# Microcontroller_1_2.net
KiCad netlist of a schematic drawn in EAGLE
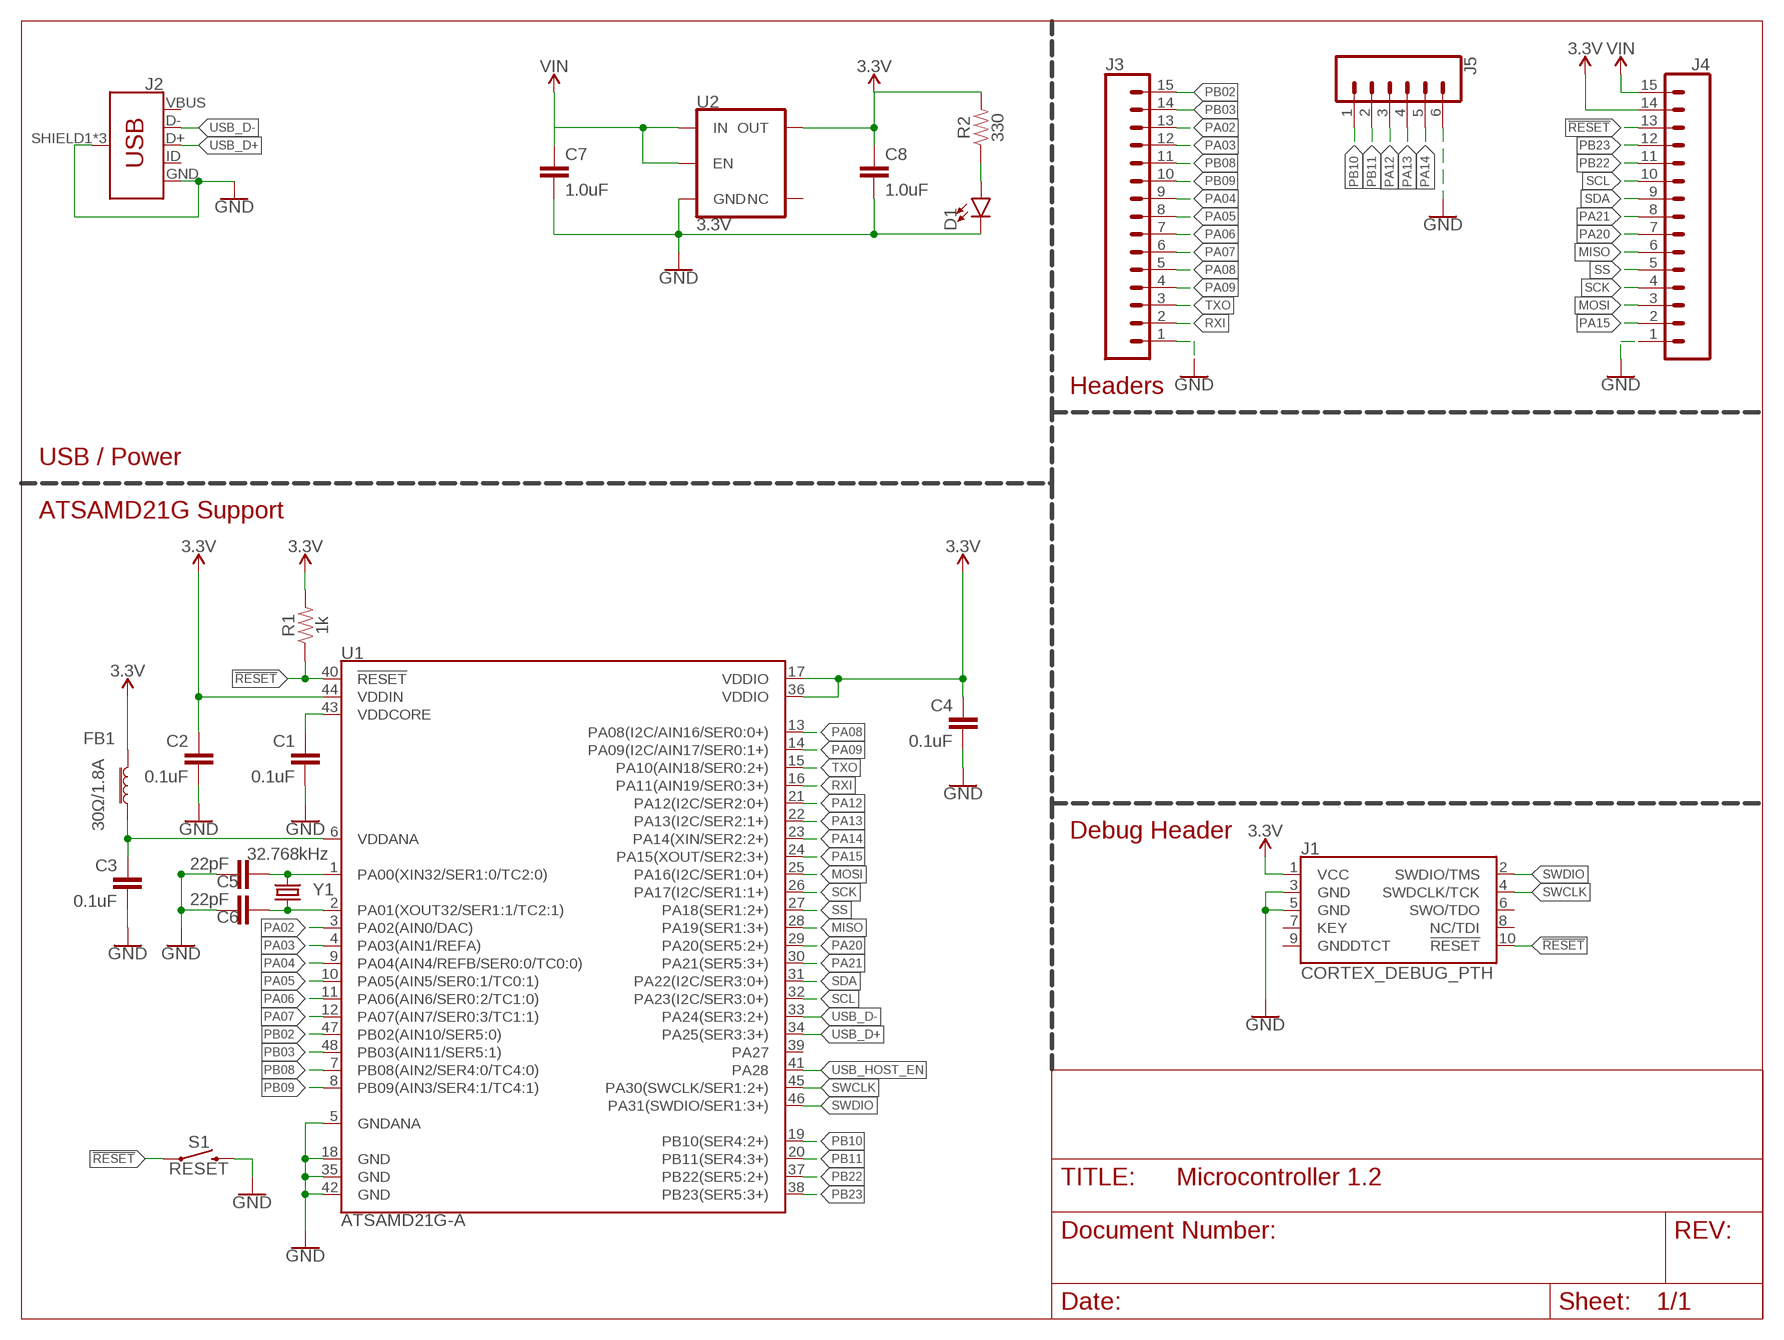
[diagram p0: schematic, sheet 1]

(export (version "E")
  (design (tool "Eeschema 10.0.6"))
  (components
    (comp (ref "C1")
      (value "0.1uF")
      (footprint "eagle-import:CAP-PTH-SMALL-KIT")
      (libsource (lib "eagle-import") (part "0.1UF-KIT-EZ-50V-20%"))
    )
    (comp (ref "C2")
      (value "0.1uF")
      (footprint "eagle-import:CAP-PTH-SMALL-KIT")
      (libsource (lib "eagle-import") (part "0.1UF-KIT-EZ-50V-20%"))
    )
    (comp (ref "C3")
      (value "0.1uF")
      (footprint "eagle-import:CAP-PTH-SMALL-KIT")
      (libsource (lib "eagle-import") (part "0.1UF-KIT-EZ-50V-20%"))
    )
    (comp (ref "C4")
      (value "0.1uF")
      (footprint "eagle-import:CAP-PTH-SMALL-KIT")
      (libsource (lib "eagle-import") (part "0.1UF-KIT-EZ-50V-20%"))
    )
    (comp (ref "C5")
      (value "22pF")
      (footprint "eagle-import:CAP-PTH-SMALL-KIT")
      (libsource (lib "eagle-import") (part "0.1UF-KIT-EZ-50V-20%"))
    )
    (comp (ref "C6")
      (value "22pF")
      (footprint "eagle-import:CAP-PTH-SMALL-KIT")
      (libsource (lib "eagle-import") (part "0.1UF-KIT-EZ-50V-20%"))
    )
    (comp (ref "C7")
      (value "1.0uF")
      (footprint "eagle-import:CAP-PTH-SMALL-KIT")
      (libsource (lib "eagle-import") (part "0.1UF-KIT-EZ-50V-20%"))
    )
    (comp (ref "C8")
      (value "1.0uF")
      (footprint "eagle-import:CAP-PTH-SMALL-KIT")
      (libsource (lib "eagle-import") (part "0.1UF-KIT-EZ-50V-20%"))
    )
    (comp (ref "D1")
      (value "LED5MM")
      (footprint "eagle-import:LED_5MM")
      (libsource (lib "eagle-import") (part "LED5MM"))
    )
    (comp (ref "FB1")
      (value "30Ω/1.8A")
      (footprint "eagle-import:0603")
      (libsource (lib "eagle-import") (part "FERRITE_BEAD-0603"))
    )
    (comp (ref "J1")
      (value "CORTEX_DEBUG_PTH")
      (footprint "eagle-import:2X5-PTH-1.27MM")
      (libsource (lib "eagle-import") (part "CORTEX_DEBUG_PTH"))
    )
    (comp (ref "J2")
      (value "USB_MICRO-B_FEMALE-SMT")
      (footprint "eagle-import:USB-B-MICRO-SMD")
      (libsource (lib "eagle-import") (part "USB_MICRO-B_FEMALE-SMT"))
    )
    (comp (ref "J3")
      (value "CONN_15LOCK")
      (footprint "eagle-import:1X15_LOCK")
      (libsource (lib "eagle-import") (part "CONN_15LOCK"))
    )
    (comp (ref "J4")
      (value "CONN_15LOCK")
      (footprint "eagle-import:1X15_LOCK")
      (libsource (lib "eagle-import") (part "CONN_15LOCK"))
    )
    (comp (ref "J5")
      (value "CONN_06LOCK")
      (footprint "eagle-import:1X06_LOCK")
      (libsource (lib "eagle-import") (part "CONN_06LOCK"))
    )
    (comp (ref "R1")
      (value "1k")
      (footprint "eagle-import:AXIAL-0.3")
      (libsource (lib "eagle-import") (part "1KOHM-HORIZ-1/4W-1%"))
    )
    (comp (ref "R2")
      (value "330")
      (footprint "eagle-import:AXIAL-0.3")
      (libsource (lib "eagle-import") (part "1KOHM-HORIZ-1/4W-1%"))
    )
    (comp (ref "S1")
      (value "RESET")
      (footprint "eagle-import:TACTILE_SWITCH_PTH_RIGHT_ANGLE_KIT")
      (libsource (lib "eagle-import") (part "MOMENTARY-SWITCH-SPST-PTH-RIGHT-ANGLE-KIT"))
    )
    (comp (ref "U1")
      (value "ATSAMD21G-A")
      (footprint "eagle-import:TQFP-48")
      (libsource (lib "eagle-import") (part "ATSAMD21G-A"))
    )
    (comp (ref "U2")
      (value "3.3V")
      (footprint "eagle-import:SOT23-5")
      (libsource (lib "eagle-import") (part "V_REG_AP2112K-3.3V"))
    )
    (comp (ref "Y1")
      (value "32.768kHz")
      (footprint "eagle-import:CRYSTAL-PTH-2X6-CYL")
      (libsource (lib "eagle-import") (part "CRYSTAL-32.768KHZPTH-2X6"))
    )
  )
  (nets
    (net (code "1") (name "/VBUS") (class "Default")
      (node (ref "J2") (pin "VBUS") (pinfunction "VBUS_VBUS") (pintype "power_in"))
    )
    (net (code "2") (name "/~{RESET}") (class "Default")
      (node (ref "J1") (pin "10") (pinfunction "~{RESET}_10") (pintype "bidirectional"))
      (node (ref "J4") (pin "13") (pinfunction "13_13") (pintype "passive"))
      (node (ref "R1") (pin "P$1") (pinfunction "1_P$1") (pintype "passive"))
      (node (ref "S1") (pin "1") (pinfunction "1_1") (pintype "passive"))
      (node (ref "U1") (pin "40") (pinfunction "~{RESET}_40") (pintype "bidirectional"))
    )
    (net (code "3") (name "3.3V") (class "Default")
      (node (ref "C2") (pin "1") (pinfunction "1_1") (pintype "passive"))
      (node (ref "C4") (pin "1") (pinfunction "1_1") (pintype "passive"))
      (node (ref "C8") (pin "1") (pinfunction "1_1") (pintype "passive"))
      (node (ref "FB1") (pin "1") (pinfunction "1_1") (pintype "passive"))
      (node (ref "J1") (pin "1") (pinfunction "VCC_1") (pintype "bidirectional"))
      (node (ref "J4") (pin "14") (pinfunction "14_14") (pintype "passive"))
      (node (ref "R1") (pin "P$2") (pinfunction "2_P$2") (pintype "passive"))
      (node (ref "R2") (pin "P$2") (pinfunction "2_P$2") (pintype "passive"))
      (node (ref "U1") (pin "17") (pinfunction "VDDIO_17") (pintype "bidirectional"))
      (node (ref "U1") (pin "36") (pinfunction "VDDIO_36") (pintype "bidirectional"))
      (node (ref "U1") (pin "44") (pinfunction "VDDIN_44") (pintype "bidirectional"))
      (node (ref "U2") (pin "5") (pinfunction "OUT_5") (pintype "passive"))
    )
    (net (code "4") (name "GND") (class "Default")
      (node (ref "C1") (pin "2") (pinfunction "2_2") (pintype "passive"))
      (node (ref "C2") (pin "2") (pinfunction "2_2") (pintype "passive"))
      (node (ref "C3") (pin "2") (pinfunction "2_2") (pintype "passive"))
      (node (ref "C4") (pin "2") (pinfunction "2_2") (pintype "passive"))
      (node (ref "C5") (pin "1") (pinfunction "1_1") (pintype "passive"))
      (node (ref "C6") (pin "1") (pinfunction "1_1") (pintype "passive"))
      (node (ref "C7") (pin "2") (pinfunction "2_2") (pintype "passive"))
      (node (ref "C8") (pin "2") (pinfunction "2_2") (pintype "passive"))
      (node (ref "D1") (pin "K") (pinfunction "C_K") (pintype "passive"))
      (node (ref "J1") (pin "3") (pinfunction "GND_3") (pintype "bidirectional"))
      (node (ref "J1") (pin "5") (pinfunction "GND_5") (pintype "bidirectional"))
      (node (ref "J2") (pin "GND") (pinfunction "GND_GND") (pintype "power_in"))
      (node (ref "J2") (pin "SHIELD1") (pinfunction "SHIELD_SHIELD1") (pintype "bidirectional"))
      (node (ref "J2") (pin "SHIELD2") (pinfunction "SHIELD_SHIELD2") (pintype "bidirectional"))
      (node (ref "J2") (pin "SHIELD3") (pinfunction "SHIELD_SHIELD3") (pintype "bidirectional"))
      (node (ref "J3") (pin "1") (pinfunction "1_1") (pintype "passive"))
      (node (ref "J4") (pin "1") (pinfunction "1_1") (pintype "passive"))
      (node (ref "J5") (pin "6") (pinfunction "6_6") (pintype "passive"))
      (node (ref "S1") (pin "2") (pinfunction "2_2") (pintype "passive"))
      (node (ref "U1") (pin "18") (pinfunction "GND_18") (pintype "bidirectional"))
      (node (ref "U1") (pin "35") (pinfunction "GND_35") (pintype "bidirectional"))
      (node (ref "U1") (pin "42") (pinfunction "GND_42") (pintype "bidirectional"))
      (node (ref "U1") (pin "5") (pinfunction "GNDANA_5") (pintype "bidirectional"))
      (node (ref "U2") (pin "2") (pinfunction "GND_2") (pintype "input"))
    )
    (net (code "5") (name "MISO") (class "Default")
      (node (ref "J4") (pin "6") (pinfunction "6_6") (pintype "passive"))
      (node (ref "U1") (pin "28") (pinfunction "PA19(SER1:3+)_28") (pintype "bidirectional"))
    )
    (net (code "6") (name "MOSI") (class "Default")
      (node (ref "J4") (pin "3") (pinfunction "3_3") (pintype "passive"))
      (node (ref "U1") (pin "25") (pinfunction "PA16(I2C/SER1:0+)_25") (pintype "bidirectional"))
    )
    (net (code "7") (name "Net-(R2-1)") (class "Default")
      (node (ref "D1") (pin "A") (pinfunction "A_A") (pintype "passive"))
      (node (ref "R2") (pin "P$1") (pinfunction "1_P$1") (pintype "passive"))
    )
    (net (code "8") (name "Net-(U1-PA00(XIN32{slash}SER1:0{slash}TC2:0))") (class "Default")
      (node (ref "C5") (pin "2") (pinfunction "2_2") (pintype "passive"))
      (node (ref "U1") (pin "1") (pinfunction "PA00(XIN32/SER1:0/TC2:0)_1") (pintype "bidirectional"))
      (node (ref "Y1") (pin "2") (pinfunction "2_2") (pintype "passive"))
    )
    (net (code "9") (name "Net-(U1-PA01(XOUT32{slash}SER1:1{slash}TC2:1))") (class "Default")
      (node (ref "C6") (pin "2") (pinfunction "2_2") (pintype "passive"))
      (node (ref "U1") (pin "2") (pinfunction "PA01(XOUT32/SER1:1/TC2:1)_2") (pintype "bidirectional"))
      (node (ref "Y1") (pin "1") (pinfunction "1_1") (pintype "passive"))
    )
    (net (code "10") (name "Net-(U1-VDDANA)") (class "Default")
      (node (ref "C3") (pin "1") (pinfunction "1_1") (pintype "passive"))
      (node (ref "FB1") (pin "2") (pinfunction "2_2") (pintype "passive"))
      (node (ref "U1") (pin "6") (pinfunction "VDDANA_6") (pintype "bidirectional"))
    )
    (net (code "11") (name "Net-(U1-VDDCORE)") (class "Default")
      (node (ref "C1") (pin "1") (pinfunction "1_1") (pintype "passive"))
      (node (ref "U1") (pin "43") (pinfunction "VDDCORE_43") (pintype "bidirectional"))
    )
    (net (code "12") (name "PA02") (class "Default")
      (node (ref "J3") (pin "13") (pinfunction "13_13") (pintype "passive"))
      (node (ref "U1") (pin "3") (pinfunction "PA02(AIN0/DAC)_3") (pintype "bidirectional"))
    )
    (net (code "13") (name "PA03") (class "Default")
      (node (ref "J3") (pin "12") (pinfunction "12_12") (pintype "passive"))
      (node (ref "U1") (pin "4") (pinfunction "PA03(AIN1/REFA)_4") (pintype "bidirectional"))
    )
    (net (code "14") (name "PA04") (class "Default")
      (node (ref "J3") (pin "9") (pinfunction "9_9") (pintype "passive"))
      (node (ref "U1") (pin "9") (pinfunction "PA04(AIN4/REFB/SER0:0/TC0:0)_9") (pintype "bidirectional"))
    )
    (net (code "15") (name "PA05") (class "Default")
      (node (ref "J3") (pin "8") (pinfunction "8_8") (pintype "passive"))
      (node (ref "U1") (pin "10") (pinfunction "PA05(AIN5/SER0:1/TC0:1)_10") (pintype "bidirectional"))
    )
    (net (code "16") (name "PA06") (class "Default")
      (node (ref "J3") (pin "7") (pinfunction "7_7") (pintype "passive"))
      (node (ref "U1") (pin "11") (pinfunction "PA06(AIN6/SER0:2/TC1:0)_11") (pintype "bidirectional"))
    )
    (net (code "17") (name "PA07") (class "Default")
      (node (ref "J3") (pin "6") (pinfunction "6_6") (pintype "passive"))
      (node (ref "U1") (pin "12") (pinfunction "PA07(AIN7/SER0:3/TC1:1)_12") (pintype "bidirectional"))
    )
    (net (code "18") (name "PA08") (class "Default")
      (node (ref "J3") (pin "5") (pinfunction "5_5") (pintype "passive"))
      (node (ref "U1") (pin "13") (pinfunction "PA08(I2C/AIN16/SER0:0+)_13") (pintype "bidirectional"))
    )
    (net (code "19") (name "PA09") (class "Default")
      (node (ref "J3") (pin "4") (pinfunction "4_4") (pintype "passive"))
      (node (ref "U1") (pin "14") (pinfunction "PA09(I2C/AIN17/SER0:1+)_14") (pintype "bidirectional"))
    )
    (net (code "20") (name "PA12") (class "Default")
      (node (ref "J5") (pin "3") (pinfunction "3_3") (pintype "passive"))
      (node (ref "U1") (pin "21") (pinfunction "PA12(I2C/SER2:0+)_21") (pintype "bidirectional"))
    )
    (net (code "21") (name "PA13") (class "Default")
      (node (ref "J5") (pin "4") (pinfunction "4_4") (pintype "passive"))
      (node (ref "U1") (pin "22") (pinfunction "PA13(I2C/SER2:1+)_22") (pintype "bidirectional"))
    )
    (net (code "22") (name "PA14") (class "Default")
      (node (ref "J5") (pin "5") (pinfunction "5_5") (pintype "passive"))
      (node (ref "U1") (pin "23") (pinfunction "PA14(XIN/SER2:2+)_23") (pintype "bidirectional"))
    )
    (net (code "23") (name "PA15") (class "Default")
      (node (ref "J4") (pin "2") (pinfunction "2_2") (pintype "passive"))
      (node (ref "U1") (pin "24") (pinfunction "PA15(XOUT/SER2:3+)_24") (pintype "bidirectional"))
    )
    (net (code "24") (name "PA20") (class "Default")
      (node (ref "J4") (pin "7") (pinfunction "7_7") (pintype "passive"))
      (node (ref "U1") (pin "29") (pinfunction "PA20(SER5:2+)_29") (pintype "bidirectional"))
    )
    (net (code "25") (name "PA21") (class "Default")
      (node (ref "J4") (pin "8") (pinfunction "8_8") (pintype "passive"))
      (node (ref "U1") (pin "30") (pinfunction "PA21(SER5:3+)_30") (pintype "bidirectional"))
    )
    (net (code "26") (name "PB02") (class "Default")
      (node (ref "J3") (pin "15") (pinfunction "15_15") (pintype "passive"))
      (node (ref "U1") (pin "47") (pinfunction "PB02(AIN10/SER5:0)_47") (pintype "bidirectional"))
    )
    (net (code "27") (name "PB03") (class "Default")
      (node (ref "J3") (pin "14") (pinfunction "14_14") (pintype "passive"))
      (node (ref "U1") (pin "48") (pinfunction "PB03(AIN11/SER5:1)_48") (pintype "bidirectional"))
    )
    (net (code "28") (name "PB08") (class "Default")
      (node (ref "J3") (pin "11") (pinfunction "11_11") (pintype "passive"))
      (node (ref "U1") (pin "7") (pinfunction "PB08(AIN2/SER4:0/TC4:0)_7") (pintype "bidirectional"))
    )
    (net (code "29") (name "PB09") (class "Default")
      (node (ref "J3") (pin "10") (pinfunction "10_10") (pintype "passive"))
      (node (ref "U1") (pin "8") (pinfunction "PB09(AIN3/SER4:1/TC4:1)_8") (pintype "bidirectional"))
    )
    (net (code "30") (name "PB10") (class "Default")
      (node (ref "J5") (pin "1") (pinfunction "1_1") (pintype "passive"))
      (node (ref "U1") (pin "19") (pinfunction "PB10(SER4:2+)_19") (pintype "bidirectional"))
    )
    (net (code "31") (name "PB11") (class "Default")
      (node (ref "J5") (pin "2") (pinfunction "2_2") (pintype "passive"))
      (node (ref "U1") (pin "20") (pinfunction "PB11(SER4:3+)_20") (pintype "bidirectional"))
    )
    (net (code "32") (name "PB22") (class "Default")
      (node (ref "J4") (pin "11") (pinfunction "11_11") (pintype "passive"))
      (node (ref "U1") (pin "37") (pinfunction "PB22(SER5:2+)_37") (pintype "bidirectional"))
    )
    (net (code "33") (name "PB23") (class "Default")
      (node (ref "J4") (pin "12") (pinfunction "12_12") (pintype "passive"))
      (node (ref "U1") (pin "38") (pinfunction "PB23(SER5:3+)_38") (pintype "bidirectional"))
    )
    (net (code "34") (name "RXI") (class "Default")
      (node (ref "J3") (pin "2") (pinfunction "2_2") (pintype "passive"))
      (node (ref "U1") (pin "16") (pinfunction "PA11(AIN19/SER0:3+)_16") (pintype "bidirectional"))
    )
    (net (code "35") (name "SCK") (class "Default")
      (node (ref "J4") (pin "4") (pinfunction "4_4") (pintype "passive"))
      (node (ref "U1") (pin "26") (pinfunction "PA17(I2C/SER1:1+)_26") (pintype "bidirectional"))
    )
    (net (code "36") (name "SCL") (class "Default")
      (node (ref "J4") (pin "10") (pinfunction "10_10") (pintype "passive"))
      (node (ref "U1") (pin "32") (pinfunction "PA23(I2C/SER3:0+)_32") (pintype "bidirectional"))
    )
    (net (code "37") (name "SDA") (class "Default")
      (node (ref "J4") (pin "9") (pinfunction "9_9") (pintype "passive"))
      (node (ref "U1") (pin "31") (pinfunction "PA22(I2C/SER3:0+)_31") (pintype "bidirectional"))
    )
    (net (code "38") (name "SS") (class "Default")
      (node (ref "J4") (pin "5") (pinfunction "5_5") (pintype "passive"))
      (node (ref "U1") (pin "27") (pinfunction "PA18(SER1:2+)_27") (pintype "bidirectional"))
    )
    (net (code "39") (name "SWCLK") (class "Default")
      (node (ref "J1") (pin "4") (pinfunction "SWDCLK/TCK_4") (pintype "bidirectional"))
      (node (ref "U1") (pin "45") (pinfunction "PA30(SWCLK/SER1:2+)_45") (pintype "bidirectional"))
    )
    (net (code "40") (name "SWDIO") (class "Default")
      (node (ref "J1") (pin "2") (pinfunction "SWDIO/TMS_2") (pintype "bidirectional"))
      (node (ref "U1") (pin "46") (pinfunction "PA31(SWDIO/SER1:3+)_46") (pintype "bidirectional"))
    )
    (net (code "41") (name "TXO") (class "Default")
      (node (ref "J3") (pin "3") (pinfunction "3_3") (pintype "passive"))
      (node (ref "U1") (pin "15") (pinfunction "PA10(AIN18/SER0:2+)_15") (pintype "bidirectional"))
    )
    (net (code "42") (name "USB_D+") (class "Default")
      (node (ref "J2") (pin "D+") (pinfunction "D+_D+") (pintype "bidirectional"))
      (node (ref "U1") (pin "34") (pinfunction "PA25(SER3:3+)_34") (pintype "bidirectional"))
    )
    (net (code "43") (name "USB_D-") (class "Default")
      (node (ref "J2") (pin "D-") (pinfunction "D-_D-") (pintype "bidirectional"))
      (node (ref "U1") (pin "33") (pinfunction "PA24(SER3:2+)_33") (pintype "bidirectional"))
    )
    (net (code "44") (name "USB_HOST_EN") (class "Default")
      (node (ref "U1") (pin "41") (pinfunction "PA28_41") (pintype "bidirectional"))
    )
    (net (code "45") (name "VIN") (class "Default")
      (node (ref "C7") (pin "1") (pinfunction "1_1") (pintype "passive"))
      (node (ref "J4") (pin "15") (pinfunction "15_15") (pintype "passive"))
      (node (ref "U2") (pin "1") (pinfunction "IN_1") (pintype "input"))
      (node (ref "U2") (pin "3") (pinfunction "EN_3") (pintype "input"))
    )
    (net (code "46") (name "unconnected-(J1-GNDDTCT-Pad9)") (class "Default")
      (node (ref "J1") (pin "9") (pinfunction "GNDDTCT_9") (pintype "bidirectional"))
    )
    (net (code "47") (name "unconnected-(J1-KEY-Pad7)") (class "Default")
      (node (ref "J1") (pin "7") (pinfunction "KEY_7") (pintype "bidirectional"))
    )
    (net (code "48") (name "unconnected-(J1-NC{slash}TDI-Pad8)") (class "Default")
      (node (ref "J1") (pin "8") (pinfunction "NC/TDI_8") (pintype "bidirectional"))
    )
    (net (code "49") (name "unconnected-(J1-SWO{slash}TDO-Pad6)") (class "Default")
      (node (ref "J1") (pin "6") (pinfunction "SWO/TDO_6") (pintype "bidirectional"))
    )
    (net (code "50") (name "unconnected-(J2-PadID)") (class "Default")
      (node (ref "J2") (pin "ID") (pinfunction "ID_ID") (pintype "bidirectional"))
    )
    (net (code "51") (name "unconnected-(U1-PA27-Pad39)") (class "Default")
      (node (ref "U1") (pin "39") (pinfunction "PA27_39") (pintype "bidirectional"))
    )
    (net (code "52") (name "unconnected-(U2-NC-Pad4)") (class "Default")
      (node (ref "U2") (pin "4") (pinfunction "NC_4") (pintype "no_connect"))
    )
  )
)
